# MCU-PCB-schematic.net
KiCad netlist of a schematic drawn in EAGLE
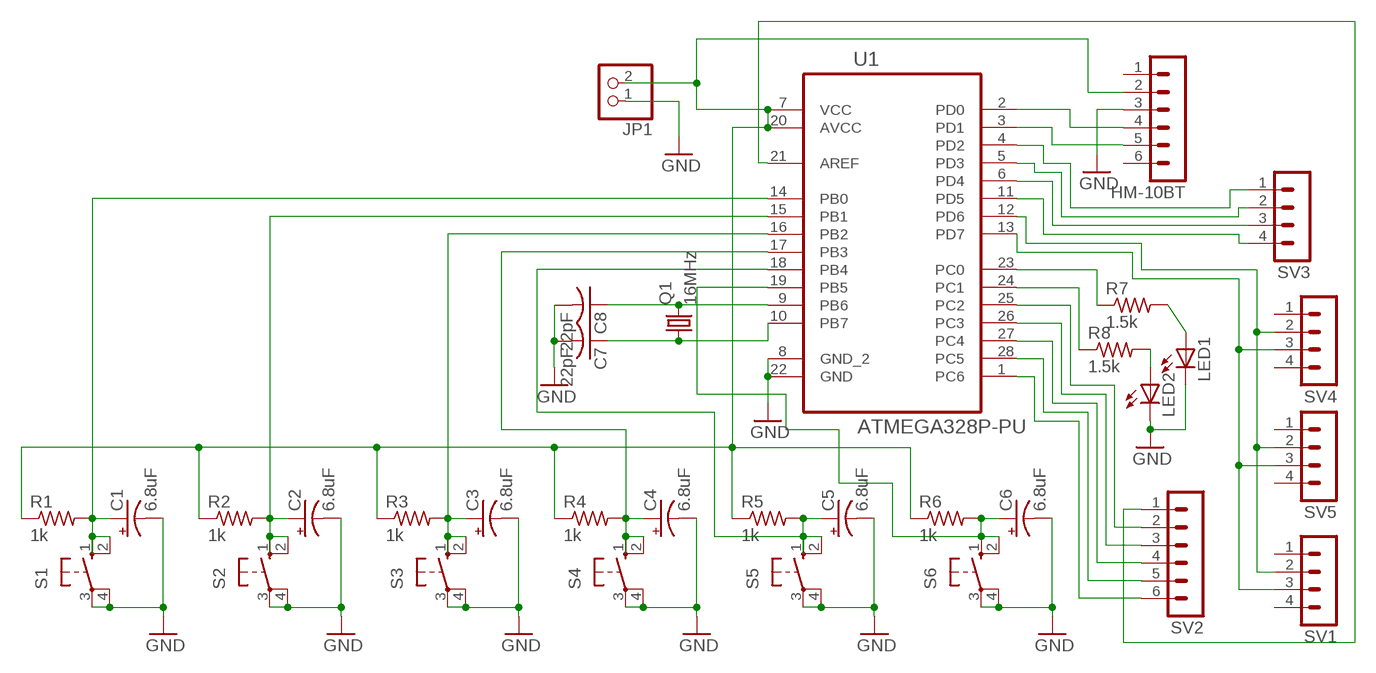
[diagram p0: schematic, sheet 1]

(export (version "E")
  (design (tool "Eeschema 10.0.6"))
  (components
    (comp (ref "C1")
      (value "6.8uF")
      (footprint "eagle-import:E2,5-5")
      (libsource (lib "eagle-import") (part "CPOL-USE2.5-5"))
    )
    (comp (ref "C2")
      (value "6.8uF")
      (footprint "eagle-import:E2,5-5")
      (libsource (lib "eagle-import") (part "CPOL-USE2.5-5"))
    )
    (comp (ref "C3")
      (value "6.8uF")
      (footprint "eagle-import:E2,5-5")
      (libsource (lib "eagle-import") (part "CPOL-USE2.5-5"))
    )
    (comp (ref "C4")
      (value "6.8uF")
      (footprint "eagle-import:E2,5-5")
      (libsource (lib "eagle-import") (part "CPOL-USE2.5-5"))
    )
    (comp (ref "C5")
      (value "6.8uF")
      (footprint "eagle-import:E2,5-5")
      (libsource (lib "eagle-import") (part "CPOL-USE2.5-5"))
    )
    (comp (ref "C6")
      (value "6.8uF")
      (footprint "eagle-import:E2,5-5")
      (libsource (lib "eagle-import") (part "CPOL-USE2.5-5"))
    )
    (comp (ref "C7")
      (value "22pF")
      (footprint "eagle-import:C025-024X044")
      (libsource (lib "eagle-import") (part "C-US025-024X044"))
    )
    (comp (ref "C8")
      (value "22pF")
      (footprint "eagle-import:C025-024X044")
      (libsource (lib "eagle-import") (part "C-US025-024X044"))
    )
    (comp (ref "HM-10BT")
      (value "MA06-1")
      (footprint "eagle-import:MA06-1")
      (libsource (lib "eagle-import") (part "MA06-1"))
    )
    (comp (ref "JP1")
      (value "PINHD-1X2")
      (footprint "eagle-import:1X02")
      (libsource (lib "eagle-import") (part "PINHD-1X2"))
    )
    (comp (ref "LED1")
      (value "LED5MM")
      (footprint "eagle-import:LED5MM")
      (libsource (lib "eagle-import") (part "LED5MM"))
    )
    (comp (ref "LED2")
      (value "LED5MM")
      (footprint "eagle-import:LED5MM")
      (libsource (lib "eagle-import") (part "LED5MM"))
    )
    (comp (ref "Q1")
      (value "16MHz")
      (footprint "eagle-import:HC49_S")
      (libsource (lib "eagle-import") (part "CRYSTALHC49S"))
    )
    (comp (ref "R1")
      (value "1k")
      (footprint "eagle-import:0207_10")
      (libsource (lib "eagle-import") (part "R-US_0207/10"))
    )
    (comp (ref "R2")
      (value "1k")
      (footprint "eagle-import:0207_10")
      (libsource (lib "eagle-import") (part "R-US_0207/10"))
    )
    (comp (ref "R3")
      (value "1k")
      (footprint "eagle-import:0207_10")
      (libsource (lib "eagle-import") (part "R-US_0207/10"))
    )
    (comp (ref "R4")
      (value "1k")
      (footprint "eagle-import:0207_10")
      (libsource (lib "eagle-import") (part "R-US_0207/10"))
    )
    (comp (ref "R5")
      (value "1k")
      (footprint "eagle-import:0207_10")
      (libsource (lib "eagle-import") (part "R-US_0207/10"))
    )
    (comp (ref "R6")
      (value "1k")
      (footprint "eagle-import:0207_10")
      (libsource (lib "eagle-import") (part "R-US_0207/10"))
    )
    (comp (ref "R7")
      (value "1.5k")
      (footprint "eagle-import:0207_10")
      (libsource (lib "eagle-import") (part "R-US_0207/10"))
    )
    (comp (ref "R8")
      (value "1.5k")
      (footprint "eagle-import:0207_10")
      (libsource (lib "eagle-import") (part "R-US_0207/10"))
    )
    (comp (ref "S1")
      (value "10-XX")
      (footprint "eagle-import:B3F-10XX")
      (fields (field (name "MPN") "B3F-1000"))
      (libsource (lib "eagle-import") (part "10-XX"))
    )
    (comp (ref "S2")
      (value "10-XX")
      (footprint "eagle-import:B3F-10XX")
      (fields (field (name "MPN") "B3F-1000"))
      (libsource (lib "eagle-import") (part "10-XX"))
    )
    (comp (ref "S3")
      (value "10-XX")
      (footprint "eagle-import:B3F-10XX")
      (fields (field (name "MPN") "B3F-1000"))
      (libsource (lib "eagle-import") (part "10-XX"))
    )
    (comp (ref "S4")
      (value "10-XX")
      (footprint "eagle-import:B3F-10XX")
      (fields (field (name "MPN") "B3F-1000"))
      (libsource (lib "eagle-import") (part "10-XX"))
    )
    (comp (ref "S5")
      (value "10-XX")
      (footprint "eagle-import:B3F-10XX")
      (fields (field (name "MPN") "B3F-1000"))
      (libsource (lib "eagle-import") (part "10-XX"))
    )
    (comp (ref "S6")
      (value "10-XX")
      (footprint "eagle-import:B3F-10XX")
      (fields (field (name "MPN") "B3F-1000"))
      (libsource (lib "eagle-import") (part "10-XX"))
    )
    (comp (ref "SV1")
      (value "MA04-1")
      (footprint "eagle-import:MA04-1")
      (libsource (lib "eagle-import") (part "MA04-1"))
    )
    (comp (ref "SV2")
      (value "MA06-1")
      (footprint "eagle-import:MA06-1")
      (libsource (lib "eagle-import") (part "MA06-1"))
    )
    (comp (ref "SV3")
      (value "MA04-1")
      (footprint "eagle-import:MA04-1")
      (libsource (lib "eagle-import") (part "MA04-1"))
    )
    (comp (ref "SV4")
      (value "MA04-1")
      (footprint "eagle-import:MA04-1")
      (libsource (lib "eagle-import") (part "MA04-1"))
    )
    (comp (ref "SV5")
      (value "MA04-1")
      (footprint "eagle-import:MA04-1")
      (libsource (lib "eagle-import") (part "MA04-1"))
    )
    (comp (ref "U1")
      (value "ATMEGA328P-PU")
      (footprint "eagle-import:DIP254P762X457-28")
      (libsource (lib "eagle-import") (part "ATMEGA328P-PU"))
    )
  )
  (nets
    (net (code "1") (name "GND") (class "Default")
      (node (ref "C1") (pin "-") (pinfunction "-_-") (pintype "passive"))
      (node (ref "C2") (pin "-") (pinfunction "-_-") (pintype "passive"))
      (node (ref "C3") (pin "-") (pinfunction "-_-") (pintype "passive"))
      (node (ref "C4") (pin "-") (pinfunction "-_-") (pintype "passive"))
      (node (ref "C5") (pin "-") (pinfunction "-_-") (pintype "passive"))
      (node (ref "C6") (pin "-") (pinfunction "-_-") (pintype "passive"))
      (node (ref "C7") (pin "2") (pinfunction "2_2") (pintype "passive"))
      (node (ref "C8") (pin "2") (pinfunction "2_2") (pintype "passive"))
      (node (ref "HM-10BT") (pin "3") (pinfunction "3_3") (pintype "passive"))
      (node (ref "JP1") (pin "1") (pinfunction "1_1") (pintype "passive"))
      (node (ref "LED1") (pin "K") (pinfunction "C_K") (pintype "passive"))
      (node (ref "LED2") (pin "K") (pinfunction "C_K") (pintype "passive"))
      (node (ref "S1") (pin "3") (pinfunction "P_3") (pintype "passive"))
      (node (ref "S1") (pin "4") (pinfunction "P1_4") (pintype "passive"))
      (node (ref "S2") (pin "3") (pinfunction "P_3") (pintype "passive"))
      (node (ref "S2") (pin "4") (pinfunction "P1_4") (pintype "passive"))
      (node (ref "S3") (pin "3") (pinfunction "P_3") (pintype "passive"))
      (node (ref "S3") (pin "4") (pinfunction "P1_4") (pintype "passive"))
      (node (ref "S4") (pin "3") (pinfunction "P_3") (pintype "passive"))
      (node (ref "S4") (pin "4") (pinfunction "P1_4") (pintype "passive"))
      (node (ref "S5") (pin "3") (pinfunction "P_3") (pintype "passive"))
      (node (ref "S5") (pin "4") (pinfunction "P1_4") (pintype "passive"))
      (node (ref "S6") (pin "3") (pinfunction "P_3") (pintype "passive"))
      (node (ref "S6") (pin "4") (pinfunction "P1_4") (pintype "passive"))
      (node (ref "U1") (pin "22") (pinfunction "GND_22") (pintype "passive"))
      (node (ref "U1") (pin "8") (pinfunction "GND_2_8") (pintype "passive"))
    )
    (net (code "2") (name "Net-(LED1-PadA)") (class "Default")
      (node (ref "LED1") (pin "A") (pinfunction "A_A") (pintype "passive"))
      (node (ref "R7") (pin "2") (pinfunction "2_2") (pintype "passive"))
    )
    (net (code "3") (name "Net-(LED2-PadA)") (class "Default")
      (node (ref "LED2") (pin "A") (pinfunction "A_A") (pintype "passive"))
      (node (ref "R8") (pin "2") (pinfunction "2_2") (pintype "passive"))
    )
    (net (code "4") (name "Net-(S1-S)") (class "Default")
      (node (ref "C1") (pin "+") (pinfunction "+_+") (pintype "passive"))
      (node (ref "R1") (pin "2") (pinfunction "2_2") (pintype "passive"))
      (node (ref "S1") (pin "1") (pinfunction "S_1") (pintype "passive"))
      (node (ref "S1") (pin "2") (pinfunction "S1_2") (pintype "passive"))
      (node (ref "U1") (pin "14") (pinfunction "PB0_14") (pintype "bidirectional"))
    )
    (net (code "5") (name "Net-(S2-S)") (class "Default")
      (node (ref "C2") (pin "+") (pinfunction "+_+") (pintype "passive"))
      (node (ref "R2") (pin "2") (pinfunction "2_2") (pintype "passive"))
      (node (ref "S2") (pin "1") (pinfunction "S_1") (pintype "passive"))
      (node (ref "S2") (pin "2") (pinfunction "S1_2") (pintype "passive"))
      (node (ref "U1") (pin "15") (pinfunction "PB1_15") (pintype "bidirectional"))
    )
    (net (code "6") (name "Net-(S3-S)") (class "Default")
      (node (ref "C3") (pin "+") (pinfunction "+_+") (pintype "passive"))
      (node (ref "R3") (pin "2") (pinfunction "2_2") (pintype "passive"))
      (node (ref "S3") (pin "1") (pinfunction "S_1") (pintype "passive"))
      (node (ref "S3") (pin "2") (pinfunction "S1_2") (pintype "passive"))
      (node (ref "U1") (pin "16") (pinfunction "PB2_16") (pintype "bidirectional"))
    )
    (net (code "7") (name "Net-(S4-S)") (class "Default")
      (node (ref "C4") (pin "+") (pinfunction "+_+") (pintype "passive"))
      (node (ref "R4") (pin "2") (pinfunction "2_2") (pintype "passive"))
      (node (ref "S4") (pin "1") (pinfunction "S_1") (pintype "passive"))
      (node (ref "S4") (pin "2") (pinfunction "S1_2") (pintype "passive"))
      (node (ref "U1") (pin "17") (pinfunction "PB3_17") (pintype "bidirectional"))
    )
    (net (code "8") (name "Net-(S5-S)") (class "Default")
      (node (ref "C5") (pin "+") (pinfunction "+_+") (pintype "passive"))
      (node (ref "R5") (pin "2") (pinfunction "2_2") (pintype "passive"))
      (node (ref "S5") (pin "1") (pinfunction "S_1") (pintype "passive"))
      (node (ref "S5") (pin "2") (pinfunction "S1_2") (pintype "passive"))
      (node (ref "U1") (pin "18") (pinfunction "PB4_18") (pintype "bidirectional"))
    )
    (net (code "9") (name "Net-(S6-S)") (class "Default")
      (node (ref "C6") (pin "+") (pinfunction "+_+") (pintype "passive"))
      (node (ref "R6") (pin "2") (pinfunction "2_2") (pintype "passive"))
      (node (ref "S6") (pin "1") (pinfunction "S_1") (pintype "passive"))
      (node (ref "S6") (pin "2") (pinfunction "S1_2") (pintype "passive"))
      (node (ref "U1") (pin "19") (pinfunction "PB5_19") (pintype "bidirectional"))
    )
    (net (code "10") (name "Net-(U1-AREF)") (class "Default")
      (node (ref "SV2") (pin "1") (pinfunction "1_1") (pintype "passive"))
      (node (ref "U1") (pin "21") (pinfunction "AREF_21") (pintype "input"))
    )
    (net (code "11") (name "Net-(U1-AVCC)") (class "Default")
      (node (ref "HM-10BT") (pin "2") (pinfunction "2_2") (pintype "passive"))
      (node (ref "JP1") (pin "2") (pinfunction "2_2") (pintype "passive"))
      (node (ref "R1") (pin "1") (pinfunction "1_1") (pintype "passive"))
      (node (ref "R2") (pin "1") (pinfunction "1_1") (pintype "passive"))
      (node (ref "R3") (pin "1") (pinfunction "1_1") (pintype "passive"))
      (node (ref "R4") (pin "1") (pinfunction "1_1") (pintype "passive"))
      (node (ref "R5") (pin "1") (pinfunction "1_1") (pintype "passive"))
      (node (ref "R6") (pin "1") (pinfunction "1_1") (pintype "passive"))
      (node (ref "U1") (pin "20") (pinfunction "AVCC_20") (pintype "power_in"))
      (node (ref "U1") (pin "7") (pinfunction "VCC_7") (pintype "power_in"))
    )
    (net (code "12") (name "Net-(U1-PB6)") (class "Default")
      (node (ref "C8") (pin "1") (pinfunction "1_1") (pintype "passive"))
      (node (ref "Q1") (pin "2") (pinfunction "2_2") (pintype "passive"))
      (node (ref "U1") (pin "9") (pinfunction "PB6_9") (pintype "bidirectional"))
    )
    (net (code "13") (name "Net-(U1-PB7)") (class "Default")
      (node (ref "C7") (pin "1") (pinfunction "1_1") (pintype "passive"))
      (node (ref "Q1") (pin "1") (pinfunction "1_1") (pintype "passive"))
      (node (ref "U1") (pin "10") (pinfunction "PB7_10") (pintype "bidirectional"))
    )
    (net (code "14") (name "Net-(U1-PC0)") (class "Default")
      (node (ref "R7") (pin "1") (pinfunction "1_1") (pintype "passive"))
      (node (ref "U1") (pin "23") (pinfunction "PC0_23") (pintype "bidirectional"))
    )
    (net (code "15") (name "Net-(U1-PC1)") (class "Default")
      (node (ref "R8") (pin "1") (pinfunction "1_1") (pintype "passive"))
      (node (ref "U1") (pin "24") (pinfunction "PC1_24") (pintype "bidirectional"))
    )
    (net (code "16") (name "Net-(U1-PC2)") (class "Default")
      (node (ref "SV2") (pin "2") (pinfunction "2_2") (pintype "passive"))
      (node (ref "U1") (pin "25") (pinfunction "PC2_25") (pintype "bidirectional"))
    )
    (net (code "17") (name "Net-(U1-PC3)") (class "Default")
      (node (ref "SV2") (pin "3") (pinfunction "3_3") (pintype "passive"))
      (node (ref "U1") (pin "26") (pinfunction "PC3_26") (pintype "bidirectional"))
    )
    (net (code "18") (name "Net-(U1-PC4)") (class "Default")
      (node (ref "SV2") (pin "4") (pinfunction "4_4") (pintype "passive"))
      (node (ref "U1") (pin "27") (pinfunction "PC4_27") (pintype "bidirectional"))
    )
    (net (code "19") (name "Net-(U1-PC5)") (class "Default")
      (node (ref "SV2") (pin "5") (pinfunction "5_5") (pintype "passive"))
      (node (ref "U1") (pin "28") (pinfunction "PC5_28") (pintype "bidirectional"))
    )
    (net (code "20") (name "Net-(U1-PC6)") (class "Default")
      (node (ref "SV2") (pin "6") (pinfunction "6_6") (pintype "passive"))
      (node (ref "U1") (pin "1") (pinfunction "PC6_1") (pintype "bidirectional"))
    )
    (net (code "21") (name "Net-(U1-PD0)") (class "Default")
      (node (ref "HM-10BT") (pin "4") (pinfunction "4_4") (pintype "passive"))
      (node (ref "U1") (pin "2") (pinfunction "PD0_2") (pintype "bidirectional"))
    )
    (net (code "22") (name "Net-(U1-PD1)") (class "Default")
      (node (ref "HM-10BT") (pin "5") (pinfunction "5_5") (pintype "passive"))
      (node (ref "U1") (pin "3") (pinfunction "PD1_3") (pintype "bidirectional"))
    )
    (net (code "23") (name "Net-(U1-PD2)") (class "Default")
      (node (ref "SV3") (pin "1") (pinfunction "1_1") (pintype "passive"))
      (node (ref "U1") (pin "4") (pinfunction "PD2_4") (pintype "bidirectional"))
    )
    (net (code "24") (name "Net-(U1-PD3)") (class "Default")
      (node (ref "SV3") (pin "2") (pinfunction "2_2") (pintype "passive"))
      (node (ref "U1") (pin "5") (pinfunction "PD3_5") (pintype "bidirectional"))
    )
    (net (code "25") (name "Net-(U1-PD4)") (class "Default")
      (node (ref "SV3") (pin "3") (pinfunction "3_3") (pintype "passive"))
      (node (ref "U1") (pin "6") (pinfunction "PD4_6") (pintype "bidirectional"))
    )
    (net (code "26") (name "Net-(U1-PD5)") (class "Default")
      (node (ref "SV3") (pin "4") (pinfunction "4_4") (pintype "passive"))
      (node (ref "U1") (pin "11") (pinfunction "PD5_11") (pintype "bidirectional"))
    )
    (net (code "27") (name "Net-(U1-PD6)") (class "Default")
      (node (ref "SV1") (pin "2") (pinfunction "2_2") (pintype "passive"))
      (node (ref "SV4") (pin "2") (pinfunction "2_2") (pintype "passive"))
      (node (ref "SV5") (pin "2") (pinfunction "2_2") (pintype "passive"))
      (node (ref "U1") (pin "12") (pinfunction "PD6_12") (pintype "bidirectional"))
    )
    (net (code "28") (name "Net-(U1-PD7)") (class "Default")
      (node (ref "SV1") (pin "3") (pinfunction "3_3") (pintype "passive"))
      (node (ref "SV4") (pin "3") (pinfunction "3_3") (pintype "passive"))
      (node (ref "SV5") (pin "3") (pinfunction "3_3") (pintype "passive"))
      (node (ref "U1") (pin "13") (pinfunction "PD7_13") (pintype "bidirectional"))
    )
    (net (code "29") (name "unconnected-(HM-10BT-Pad1)") (class "Default")
      (node (ref "HM-10BT") (pin "1") (pinfunction "1_1") (pintype "passive"))
    )
    (net (code "30") (name "unconnected-(HM-10BT-Pad6)") (class "Default")
      (node (ref "HM-10BT") (pin "6") (pinfunction "6_6") (pintype "passive"))
    )
    (net (code "31") (name "unconnected-(SV1-Pad1)") (class "Default")
      (node (ref "SV1") (pin "1") (pinfunction "1_1") (pintype "passive"))
    )
    (net (code "32") (name "unconnected-(SV1-Pad4)") (class "Default")
      (node (ref "SV1") (pin "4") (pinfunction "4_4") (pintype "passive"))
    )
    (net (code "33") (name "unconnected-(SV4-Pad1)") (class "Default")
      (node (ref "SV4") (pin "1") (pinfunction "1_1") (pintype "passive"))
    )
    (net (code "34") (name "unconnected-(SV4-Pad4)") (class "Default")
      (node (ref "SV4") (pin "4") (pinfunction "4_4") (pintype "passive"))
    )
    (net (code "35") (name "unconnected-(SV5-Pad1)") (class "Default")
      (node (ref "SV5") (pin "1") (pinfunction "1_1") (pintype "passive"))
    )
    (net (code "36") (name "unconnected-(SV5-Pad4)") (class "Default")
      (node (ref "SV5") (pin "4") (pinfunction "4_4") (pintype "passive"))
    )
  )
)
